# s-tuner_prototype.net
KiCad netlist of a schematic drawn in EAGLE
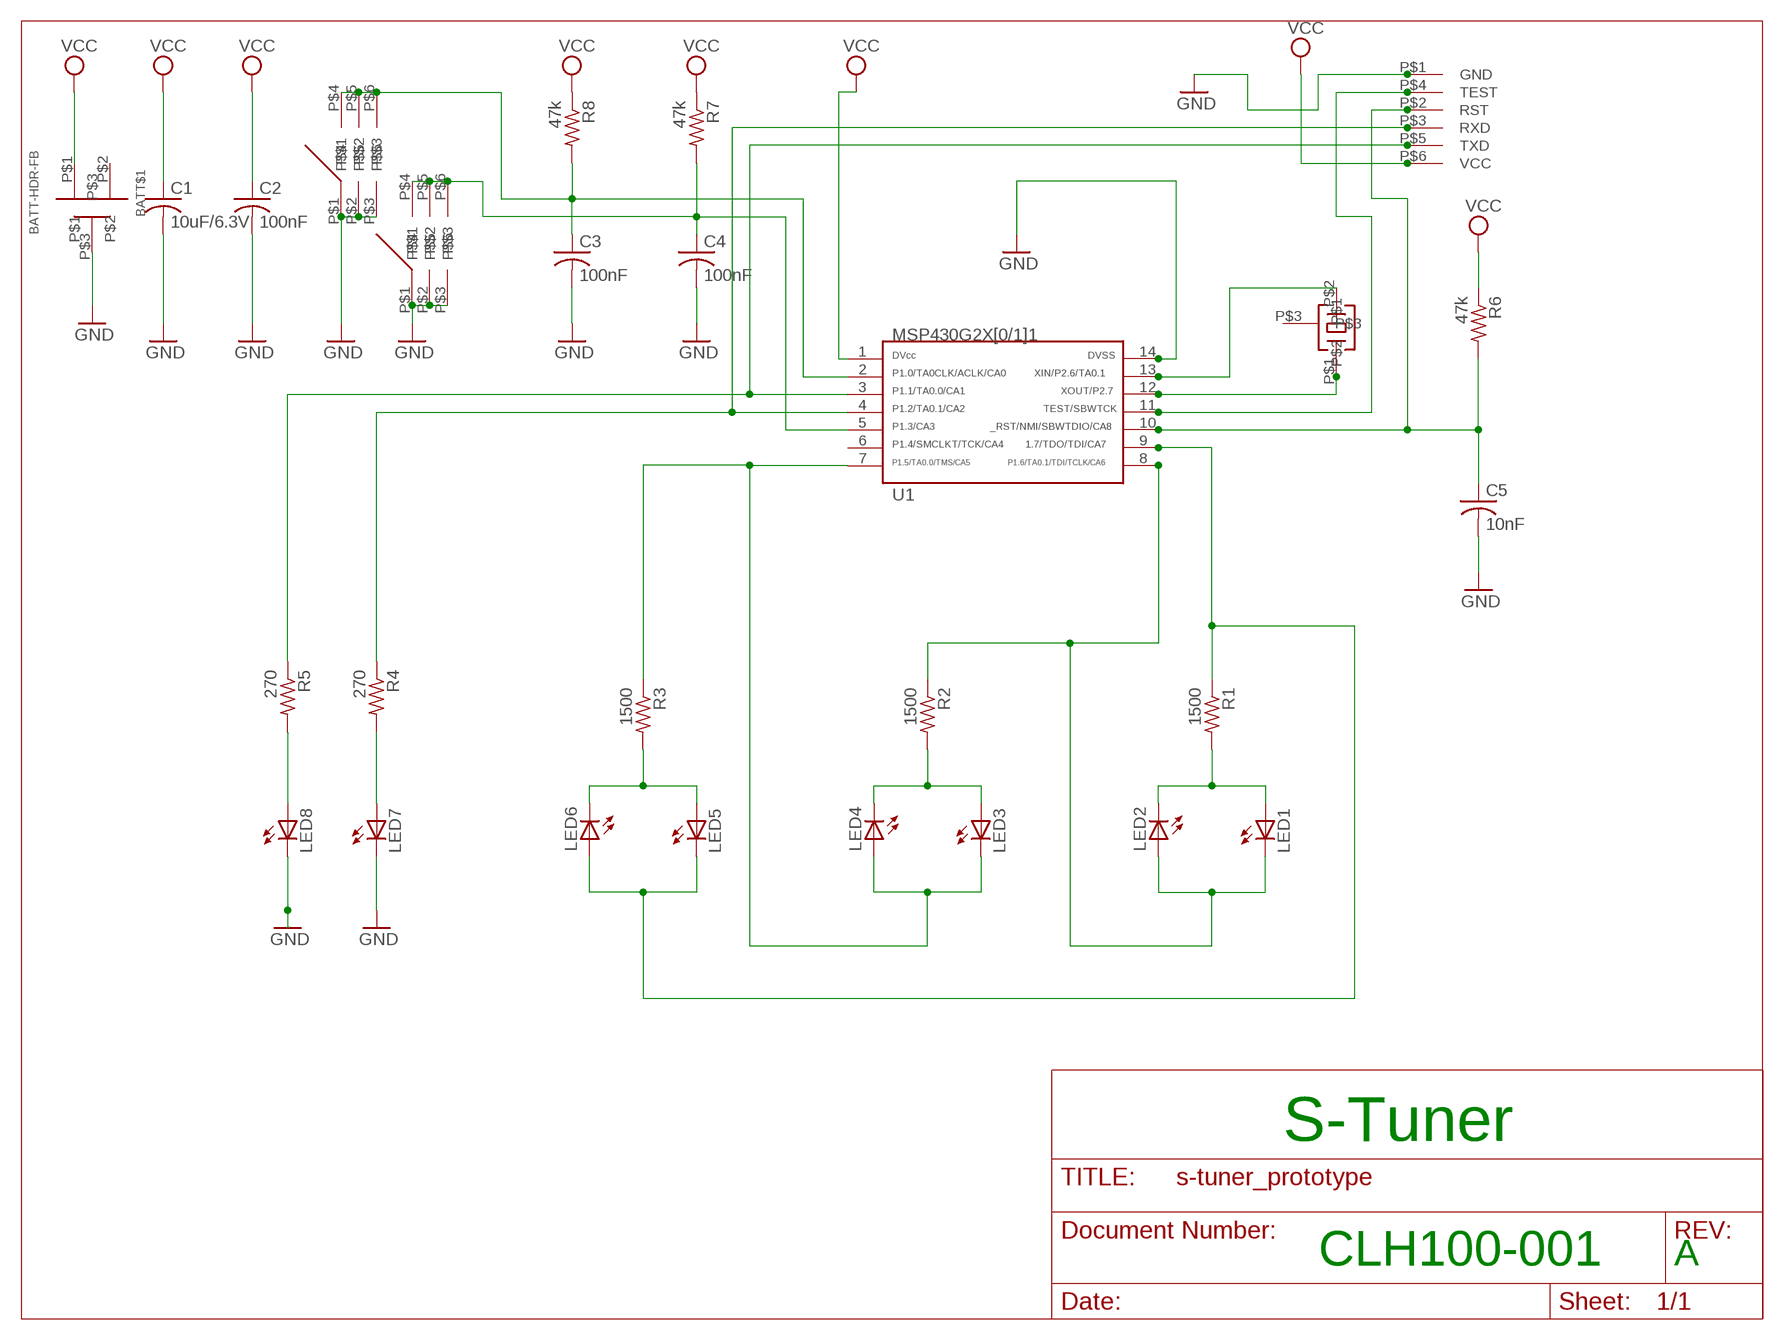
[diagram p0: schematic, sheet 1]

(export (version "E")
  (design (tool "Eeschema 10.0.6"))
  (components
    (comp (ref "BATT1")
      (value "BATT1")
      (footprint "eagle-import:BATT-HDR-FB")
      (libsource (lib "eagle-import") (part "BATT-HDR-FB"))
    )
    (comp (ref "C1")
      (value "10uF/6.3V")
      (footprint "eagle-import:C1206K")
      (libsource (lib "eagle-import") (part "C-USC1206K"))
    )
    (comp (ref "C2")
      (value "100nF")
      (footprint "eagle-import:C0603")
      (libsource (lib "eagle-import") (part "resistor_C-USC0603"))
    )
    (comp (ref "C3")
      (value "100nF")
      (footprint "eagle-import:C0603")
      (libsource (lib "eagle-import") (part "resistor_C-USC0603"))
    )
    (comp (ref "C4")
      (value "100nF")
      (footprint "eagle-import:C0603")
      (libsource (lib "eagle-import") (part "resistor_C-USC0603"))
    )
    (comp (ref "C5")
      (value "10nF")
      (footprint "eagle-import:C0603")
      (libsource (lib "eagle-import") (part "resistor_C-USC0603"))
    )
    (comp (ref "LED1")
      (value "LEDSML0805")
      (footprint "eagle-import:SML0805")
      (libsource (lib "eagle-import") (part "LEDSML0805"))
    )
    (comp (ref "LED2")
      (value "LEDSML0805")
      (footprint "eagle-import:SML0805")
      (libsource (lib "eagle-import") (part "LEDSML0805"))
    )
    (comp (ref "LED3")
      (value "LEDSML0805")
      (footprint "eagle-import:SML0805")
      (libsource (lib "eagle-import") (part "LEDSML0805"))
    )
    (comp (ref "LED4")
      (value "LEDSML0805")
      (footprint "eagle-import:SML0805")
      (libsource (lib "eagle-import") (part "LEDSML0805"))
    )
    (comp (ref "LED5")
      (value "LEDSML0805")
      (footprint "eagle-import:SML0805")
      (libsource (lib "eagle-import") (part "LEDSML0805"))
    )
    (comp (ref "LED6")
      (value "LEDSML0805")
      (footprint "eagle-import:SML0805")
      (libsource (lib "eagle-import") (part "LEDSML0805"))
    )
    (comp (ref "LED7")
      (value "LED3MM")
      (footprint "eagle-import:LED3MM")
      (libsource (lib "eagle-import") (part "LED3MM"))
    )
    (comp (ref "LED8")
      (value "LED3MM")
      (footprint "eagle-import:LED3MM")
      (libsource (lib "eagle-import") (part "LED3MM"))
    )
    (comp (ref "R1")
      (value "1500")
      (footprint "eagle-import:R0603")
      (libsource (lib "eagle-import") (part "R-US_R0603"))
    )
    (comp (ref "R2")
      (value "1500")
      (footprint "eagle-import:R0603")
      (libsource (lib "eagle-import") (part "R-US_R0603"))
    )
    (comp (ref "R3")
      (value "1500")
      (footprint "eagle-import:R0603")
      (libsource (lib "eagle-import") (part "R-US_R0603"))
    )
    (comp (ref "R4")
      (value "270")
      (footprint "eagle-import:R0603")
      (libsource (lib "eagle-import") (part "R-US_R0603"))
    )
    (comp (ref "R5")
      (value "270")
      (footprint "eagle-import:R0603")
      (libsource (lib "eagle-import") (part "R-US_R0603"))
    )
    (comp (ref "R6")
      (value "47k")
      (footprint "eagle-import:R0603")
      (libsource (lib "eagle-import") (part "R-US_R0603"))
    )
    (comp (ref "R7")
      (value "47k")
      (footprint "eagle-import:R0603")
      (libsource (lib "eagle-import") (part "R-US_R0603"))
    )
    (comp (ref "R8")
      (value "47k")
      (footprint "eagle-import:R0603")
      (libsource (lib "eagle-import") (part "R-US_R0603"))
    )
    (comp (ref "SW1")
      (value "POLYCASE_FINGER_TRACE")
      (footprint "eagle-import:POLYCASE_FINGER_TRACE")
      (libsource (lib "eagle-import") (part "POLYCASE_FINGER_TRACE"))
    )
    (comp (ref "SW2")
      (value "POLYCASE_FINGER_TRACE")
      (footprint "eagle-import:POLYCASE_FINGER_TRACE")
      (libsource (lib "eagle-import") (part "POLYCASE_FINGER_TRACE"))
    )
    (comp (ref "U$3")
      (value "PROGRAMMING_HEADER")
      (footprint "eagle-import:PROGRAMMING_HEADER")
      (libsource (lib "eagle-import") (part "PROGRAMMING_HEADER"))
    )
    (comp (ref "U1")
      (value "G2X[0/1]1---PW14")
      (footprint "eagle-import:PW14")
      (libsource (lib "eagle-import") (part "G2X[0/1]1---PW14"))
    )
    (comp (ref "U2")
      (value "MICROCRYSTAL_32K")
      (footprint "eagle-import:MICROCRYSTAL_32K")
      (libsource (lib "eagle-import") (part "MICROCRYSTAL_32K"))
    )
  )
  (nets
    (net (code "1") (name "GND") (class "Default")
      (node (ref "BATT1") (pin "P$3") (pinfunction "P$3_P$3") (pintype "bidirectional"))
      (node (ref "C1") (pin "2") (pinfunction "2_2") (pintype "passive"))
      (node (ref "C2") (pin "2") (pinfunction "2_2") (pintype "passive"))
      (node (ref "C3") (pin "2") (pinfunction "2_2") (pintype "passive"))
      (node (ref "C4") (pin "2") (pinfunction "2_2") (pintype "passive"))
      (node (ref "C5") (pin "2") (pinfunction "2_2") (pintype "passive"))
      (node (ref "LED7") (pin "K") (pinfunction "C_K") (pintype "passive"))
      (node (ref "LED8") (pin "K") (pinfunction "C_K") (pintype "passive"))
      (node (ref "SW1") (pin "P$1") (pinfunction "P$1_P$1") (pintype "bidirectional"))
      (node (ref "SW1") (pin "P$2") (pinfunction "P$2_P$2") (pintype "bidirectional"))
      (node (ref "SW1") (pin "P$3") (pinfunction "P$3_P$3") (pintype "bidirectional"))
      (node (ref "SW2") (pin "P$1") (pinfunction "P$1_P$1") (pintype "bidirectional"))
      (node (ref "SW2") (pin "P$2") (pinfunction "P$2_P$2") (pintype "bidirectional"))
      (node (ref "SW2") (pin "P$3") (pinfunction "P$3_P$3") (pintype "bidirectional"))
      (node (ref "U$3") (pin "P$1") (pinfunction "GND_P$1") (pintype "bidirectional"))
      (node (ref "U1") (pin "14") (pinfunction "14_14") (pintype "bidirectional"))
    )
    (net (code "2") (name "Net-(C3-Pad1)") (class "Default")
      (node (ref "C3") (pin "1") (pinfunction "1_1") (pintype "passive"))
      (node (ref "R8") (pin "2") (pinfunction "2_2") (pintype "passive"))
      (node (ref "SW1") (pin "P$4") (pinfunction "P$4_P$4") (pintype "bidirectional"))
      (node (ref "SW1") (pin "P$5") (pinfunction "P$5_P$5") (pintype "bidirectional"))
      (node (ref "SW1") (pin "P$6") (pinfunction "P$6_P$6") (pintype "bidirectional"))
      (node (ref "U1") (pin "2") (pinfunction "2_2") (pintype "bidirectional"))
    )
    (net (code "3") (name "Net-(C4-Pad1)") (class "Default")
      (node (ref "C4") (pin "1") (pinfunction "1_1") (pintype "passive"))
      (node (ref "R7") (pin "2") (pinfunction "2_2") (pintype "passive"))
      (node (ref "SW2") (pin "P$4") (pinfunction "P$4_P$4") (pintype "bidirectional"))
      (node (ref "SW2") (pin "P$5") (pinfunction "P$5_P$5") (pintype "bidirectional"))
      (node (ref "SW2") (pin "P$6") (pinfunction "P$6_P$6") (pintype "bidirectional"))
      (node (ref "U1") (pin "5") (pinfunction "5_5") (pintype "bidirectional"))
    )
    (net (code "4") (name "Net-(LED1-PadA)") (class "Default")
      (node (ref "LED1") (pin "A") (pinfunction "A_A") (pintype "passive"))
      (node (ref "LED2") (pin "C") (pinfunction "C_C") (pintype "passive"))
      (node (ref "R1") (pin "2") (pinfunction "2_2") (pintype "passive"))
    )
    (net (code "5") (name "Net-(LED1-PadC)") (class "Default")
      (node (ref "LED1") (pin "C") (pinfunction "C_C") (pintype "passive"))
      (node (ref "LED2") (pin "A") (pinfunction "A_A") (pintype "passive"))
      (node (ref "R2") (pin "1") (pinfunction "1_1") (pintype "passive"))
      (node (ref "U1") (pin "8") (pinfunction "8_8") (pintype "bidirectional"))
    )
    (net (code "6") (name "Net-(LED3-PadA)") (class "Default")
      (node (ref "LED3") (pin "A") (pinfunction "A_A") (pintype "passive"))
      (node (ref "LED4") (pin "C") (pinfunction "C_C") (pintype "passive"))
      (node (ref "R2") (pin "2") (pinfunction "2_2") (pintype "passive"))
    )
    (net (code "7") (name "Net-(LED3-PadC)") (class "Default")
      (node (ref "LED3") (pin "C") (pinfunction "C_C") (pintype "passive"))
      (node (ref "LED4") (pin "A") (pinfunction "A_A") (pintype "passive"))
      (node (ref "R3") (pin "1") (pinfunction "1_1") (pintype "passive"))
      (node (ref "U1") (pin "7") (pinfunction "7_7") (pintype "bidirectional"))
    )
    (net (code "8") (name "Net-(LED5-PadA)") (class "Default")
      (node (ref "LED5") (pin "A") (pinfunction "A_A") (pintype "passive"))
      (node (ref "LED6") (pin "C") (pinfunction "C_C") (pintype "passive"))
      (node (ref "R3") (pin "2") (pinfunction "2_2") (pintype "passive"))
    )
    (net (code "9") (name "Net-(LED5-PadC)") (class "Default")
      (node (ref "LED5") (pin "C") (pinfunction "C_C") (pintype "passive"))
      (node (ref "LED6") (pin "A") (pinfunction "A_A") (pintype "passive"))
      (node (ref "R1") (pin "1") (pinfunction "1_1") (pintype "passive"))
      (node (ref "U1") (pin "9") (pinfunction "9_9") (pintype "bidirectional"))
    )
    (net (code "10") (name "Net-(LED7-PadA)") (class "Default")
      (node (ref "LED7") (pin "A") (pinfunction "A_A") (pintype "passive"))
      (node (ref "R4") (pin "2") (pinfunction "2_2") (pintype "passive"))
    )
    (net (code "11") (name "Net-(LED8-PadA)") (class "Default")
      (node (ref "LED8") (pin "A") (pinfunction "A_A") (pintype "passive"))
      (node (ref "R5") (pin "2") (pinfunction "2_2") (pintype "passive"))
    )
    (net (code "12") (name "Net-(U$3-RST)") (class "Default")
      (node (ref "C5") (pin "1") (pinfunction "1_1") (pintype "passive"))
      (node (ref "R6") (pin "2") (pinfunction "2_2") (pintype "passive"))
      (node (ref "U$3") (pin "P$2") (pinfunction "RST_P$2") (pintype "bidirectional"))
      (node (ref "U1") (pin "10") (pinfunction "10_10") (pintype "bidirectional"))
    )
    (net (code "13") (name "Net-(U$3-RXD)") (class "Default")
      (node (ref "R4") (pin "1") (pinfunction "1_1") (pintype "passive"))
      (node (ref "U$3") (pin "P$3") (pinfunction "RXD_P$3") (pintype "bidirectional"))
      (node (ref "U1") (pin "4") (pinfunction "4_4") (pintype "bidirectional"))
    )
    (net (code "14") (name "Net-(U$3-TEST)") (class "Default")
      (node (ref "U$3") (pin "P$4") (pinfunction "TEST_P$4") (pintype "bidirectional"))
      (node (ref "U1") (pin "11") (pinfunction "11_11") (pintype "bidirectional"))
    )
    (net (code "15") (name "Net-(U$3-TXD)") (class "Default")
      (node (ref "R5") (pin "1") (pinfunction "1_1") (pintype "passive"))
      (node (ref "U$3") (pin "P$5") (pinfunction "TXD_P$5") (pintype "bidirectional"))
      (node (ref "U1") (pin "3") (pinfunction "3_3") (pintype "bidirectional"))
    )
    (net (code "16") (name "Net-(U1-Pad12)") (class "Default")
      (node (ref "U1") (pin "12") (pinfunction "12_12") (pintype "bidirectional"))
      (node (ref "U2") (pin "P$1") (pinfunction "P$1_P$1") (pintype "bidirectional"))
    )
    (net (code "17") (name "Net-(U1-Pad13)") (class "Default")
      (node (ref "U1") (pin "13") (pinfunction "13_13") (pintype "bidirectional"))
      (node (ref "U2") (pin "P$2") (pinfunction "P$2_P$2") (pintype "bidirectional"))
    )
    (net (code "18") (name "VCC") (class "Default")
      (node (ref "BATT1") (pin "P$1") (pinfunction "P$1_P$1") (pintype "bidirectional"))
      (node (ref "C1") (pin "1") (pinfunction "1_1") (pintype "passive"))
      (node (ref "C2") (pin "1") (pinfunction "1_1") (pintype "passive"))
      (node (ref "R6") (pin "1") (pinfunction "1_1") (pintype "passive"))
      (node (ref "R7") (pin "1") (pinfunction "1_1") (pintype "passive"))
      (node (ref "R8") (pin "1") (pinfunction "1_1") (pintype "passive"))
      (node (ref "U$3") (pin "P$6") (pinfunction "VCC_P$6") (pintype "bidirectional"))
      (node (ref "U1") (pin "1") (pinfunction "1_1") (pintype "bidirectional"))
    )
    (net (code "19") (name "unconnected-(BATT1-PadP$2)") (class "Default")
      (node (ref "BATT1") (pin "P$2") (pinfunction "P$2_P$2") (pintype "bidirectional"))
    )
    (net (code "20") (name "unconnected-(U1-Pad6)") (class "Default")
      (node (ref "U1") (pin "6") (pinfunction "6_6") (pintype "bidirectional"))
    )
    (net (code "21") (name "unconnected-(U2-PadP$3)") (class "Default")
      (node (ref "U2") (pin "P$3") (pinfunction "P$3_P$3") (pintype "bidirectional"))
    )
  )
)
